# SCH_XILINX_JTAG-N_2022-10-28.net
KiCad netlist of a schematic drawn in EasyEDA
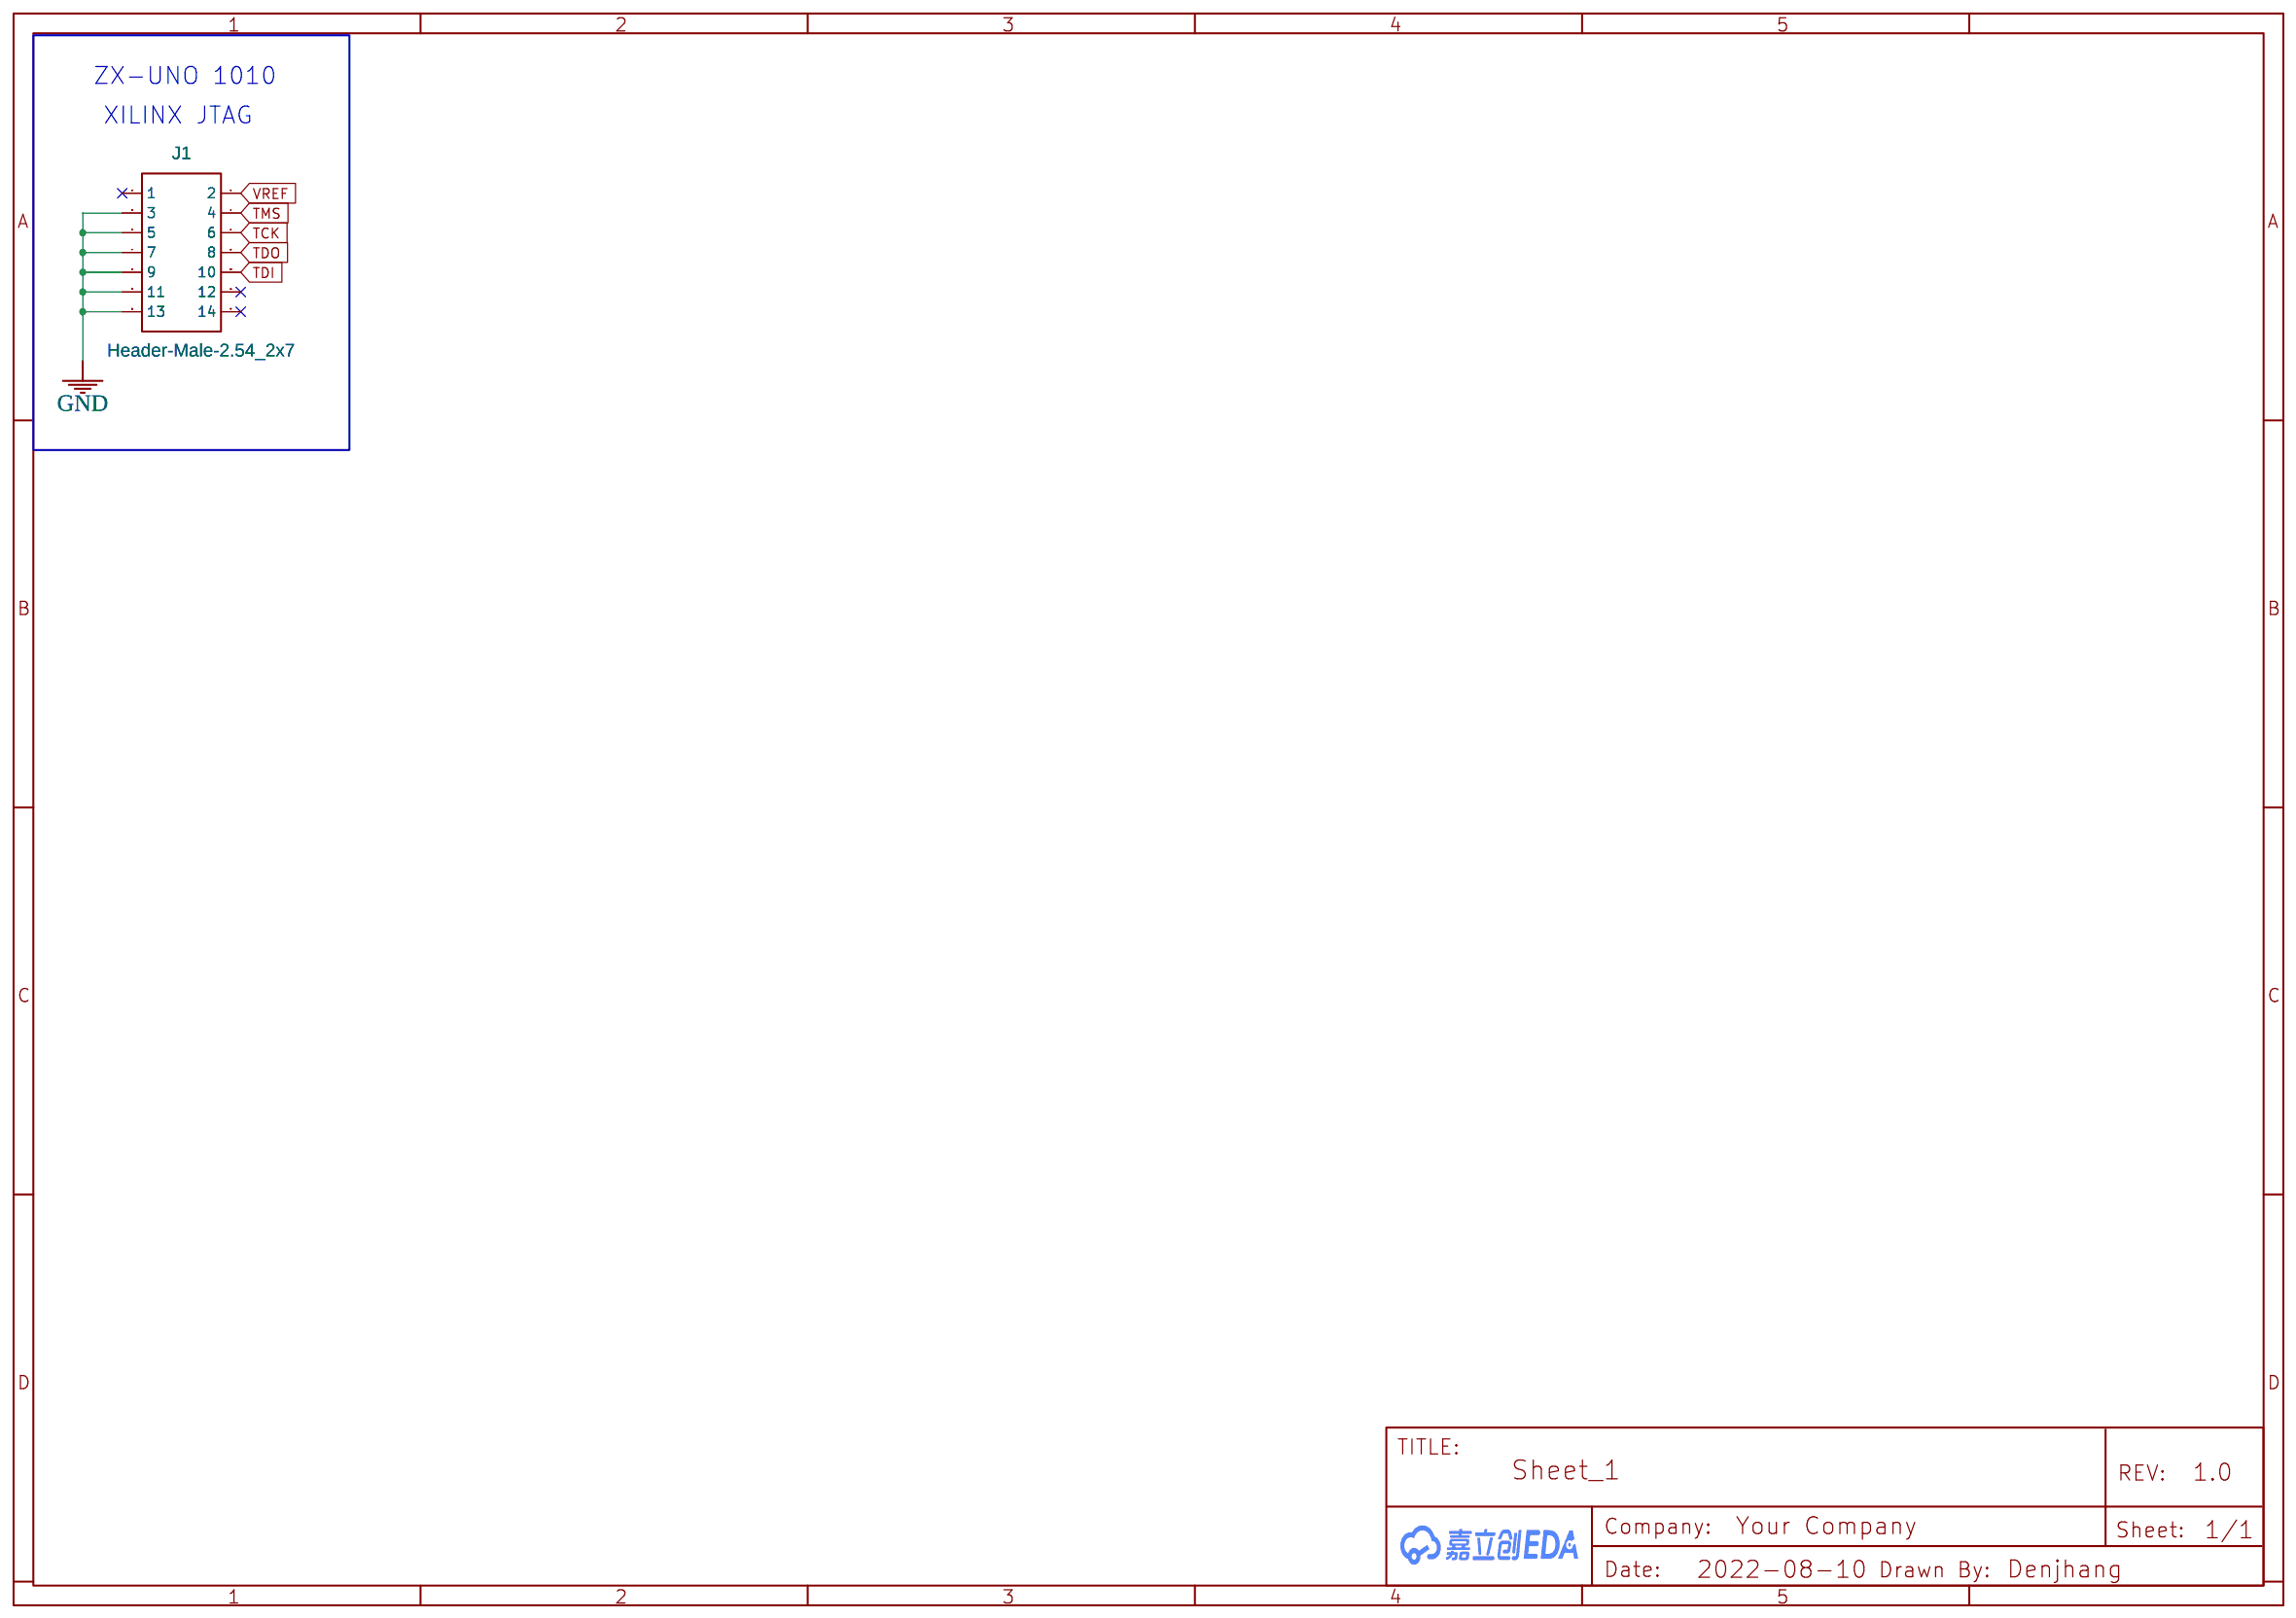
[diagram p0: MAIN]
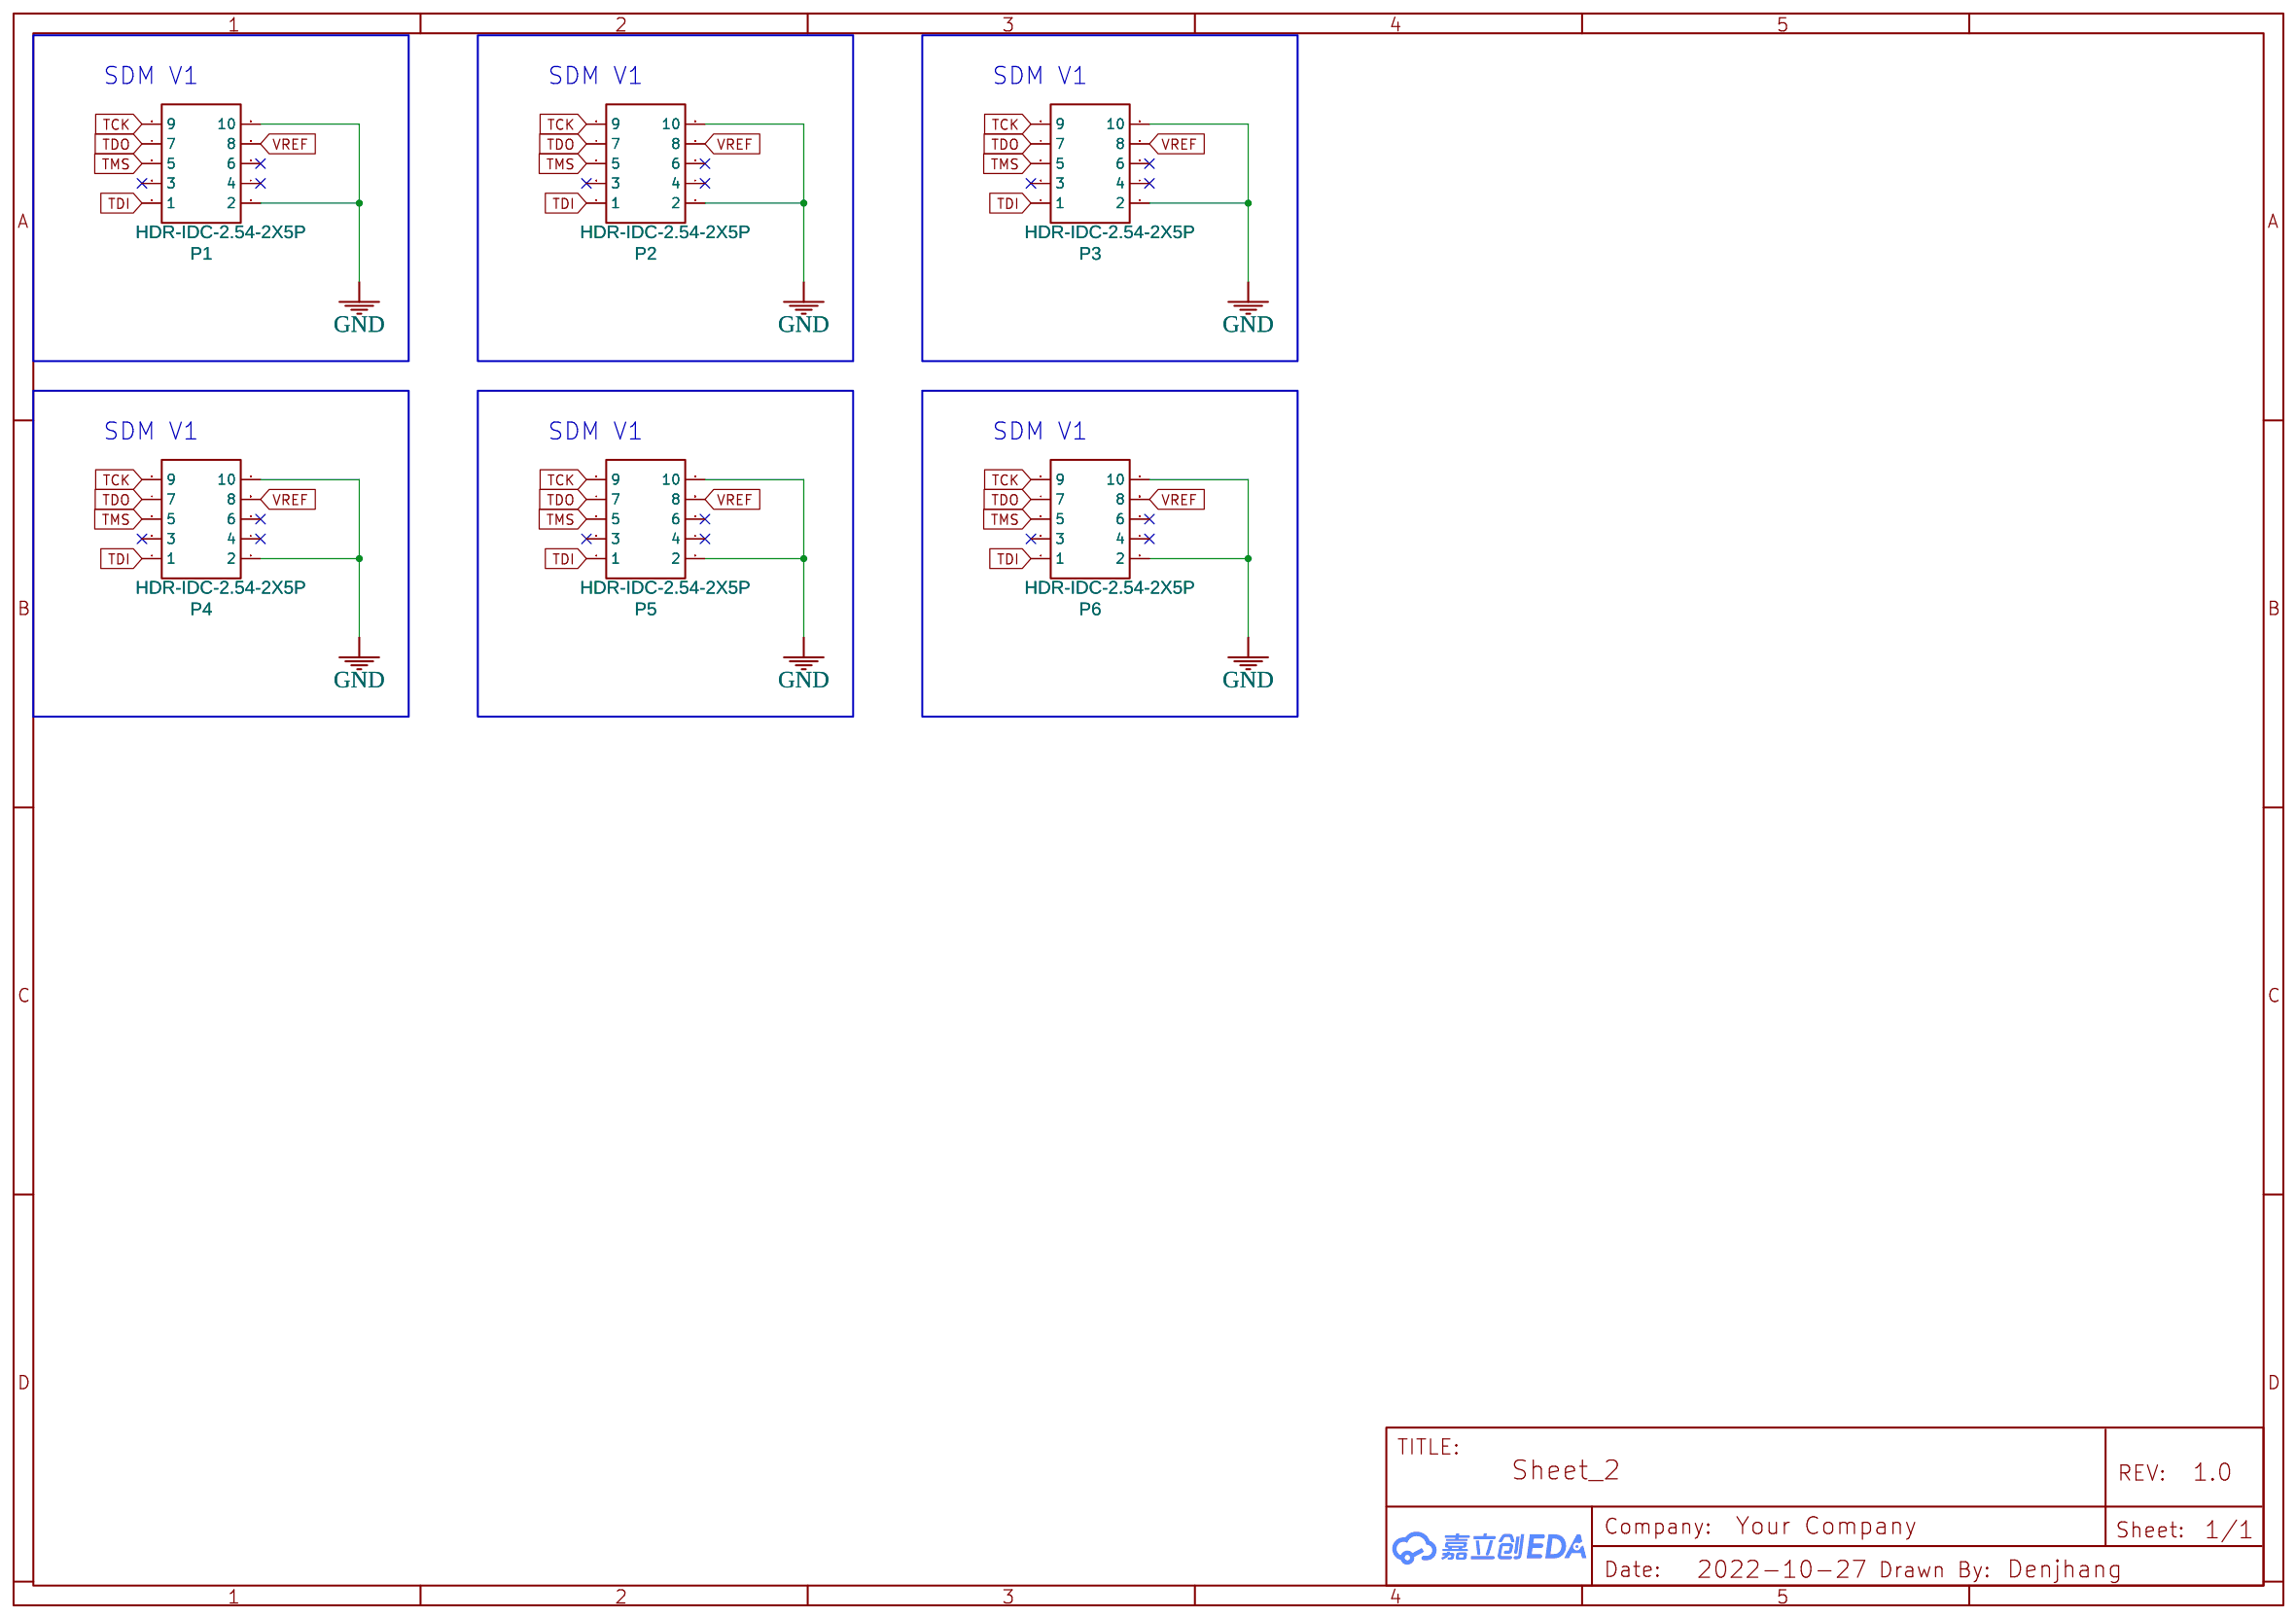
[diagram p1: SDMV1]
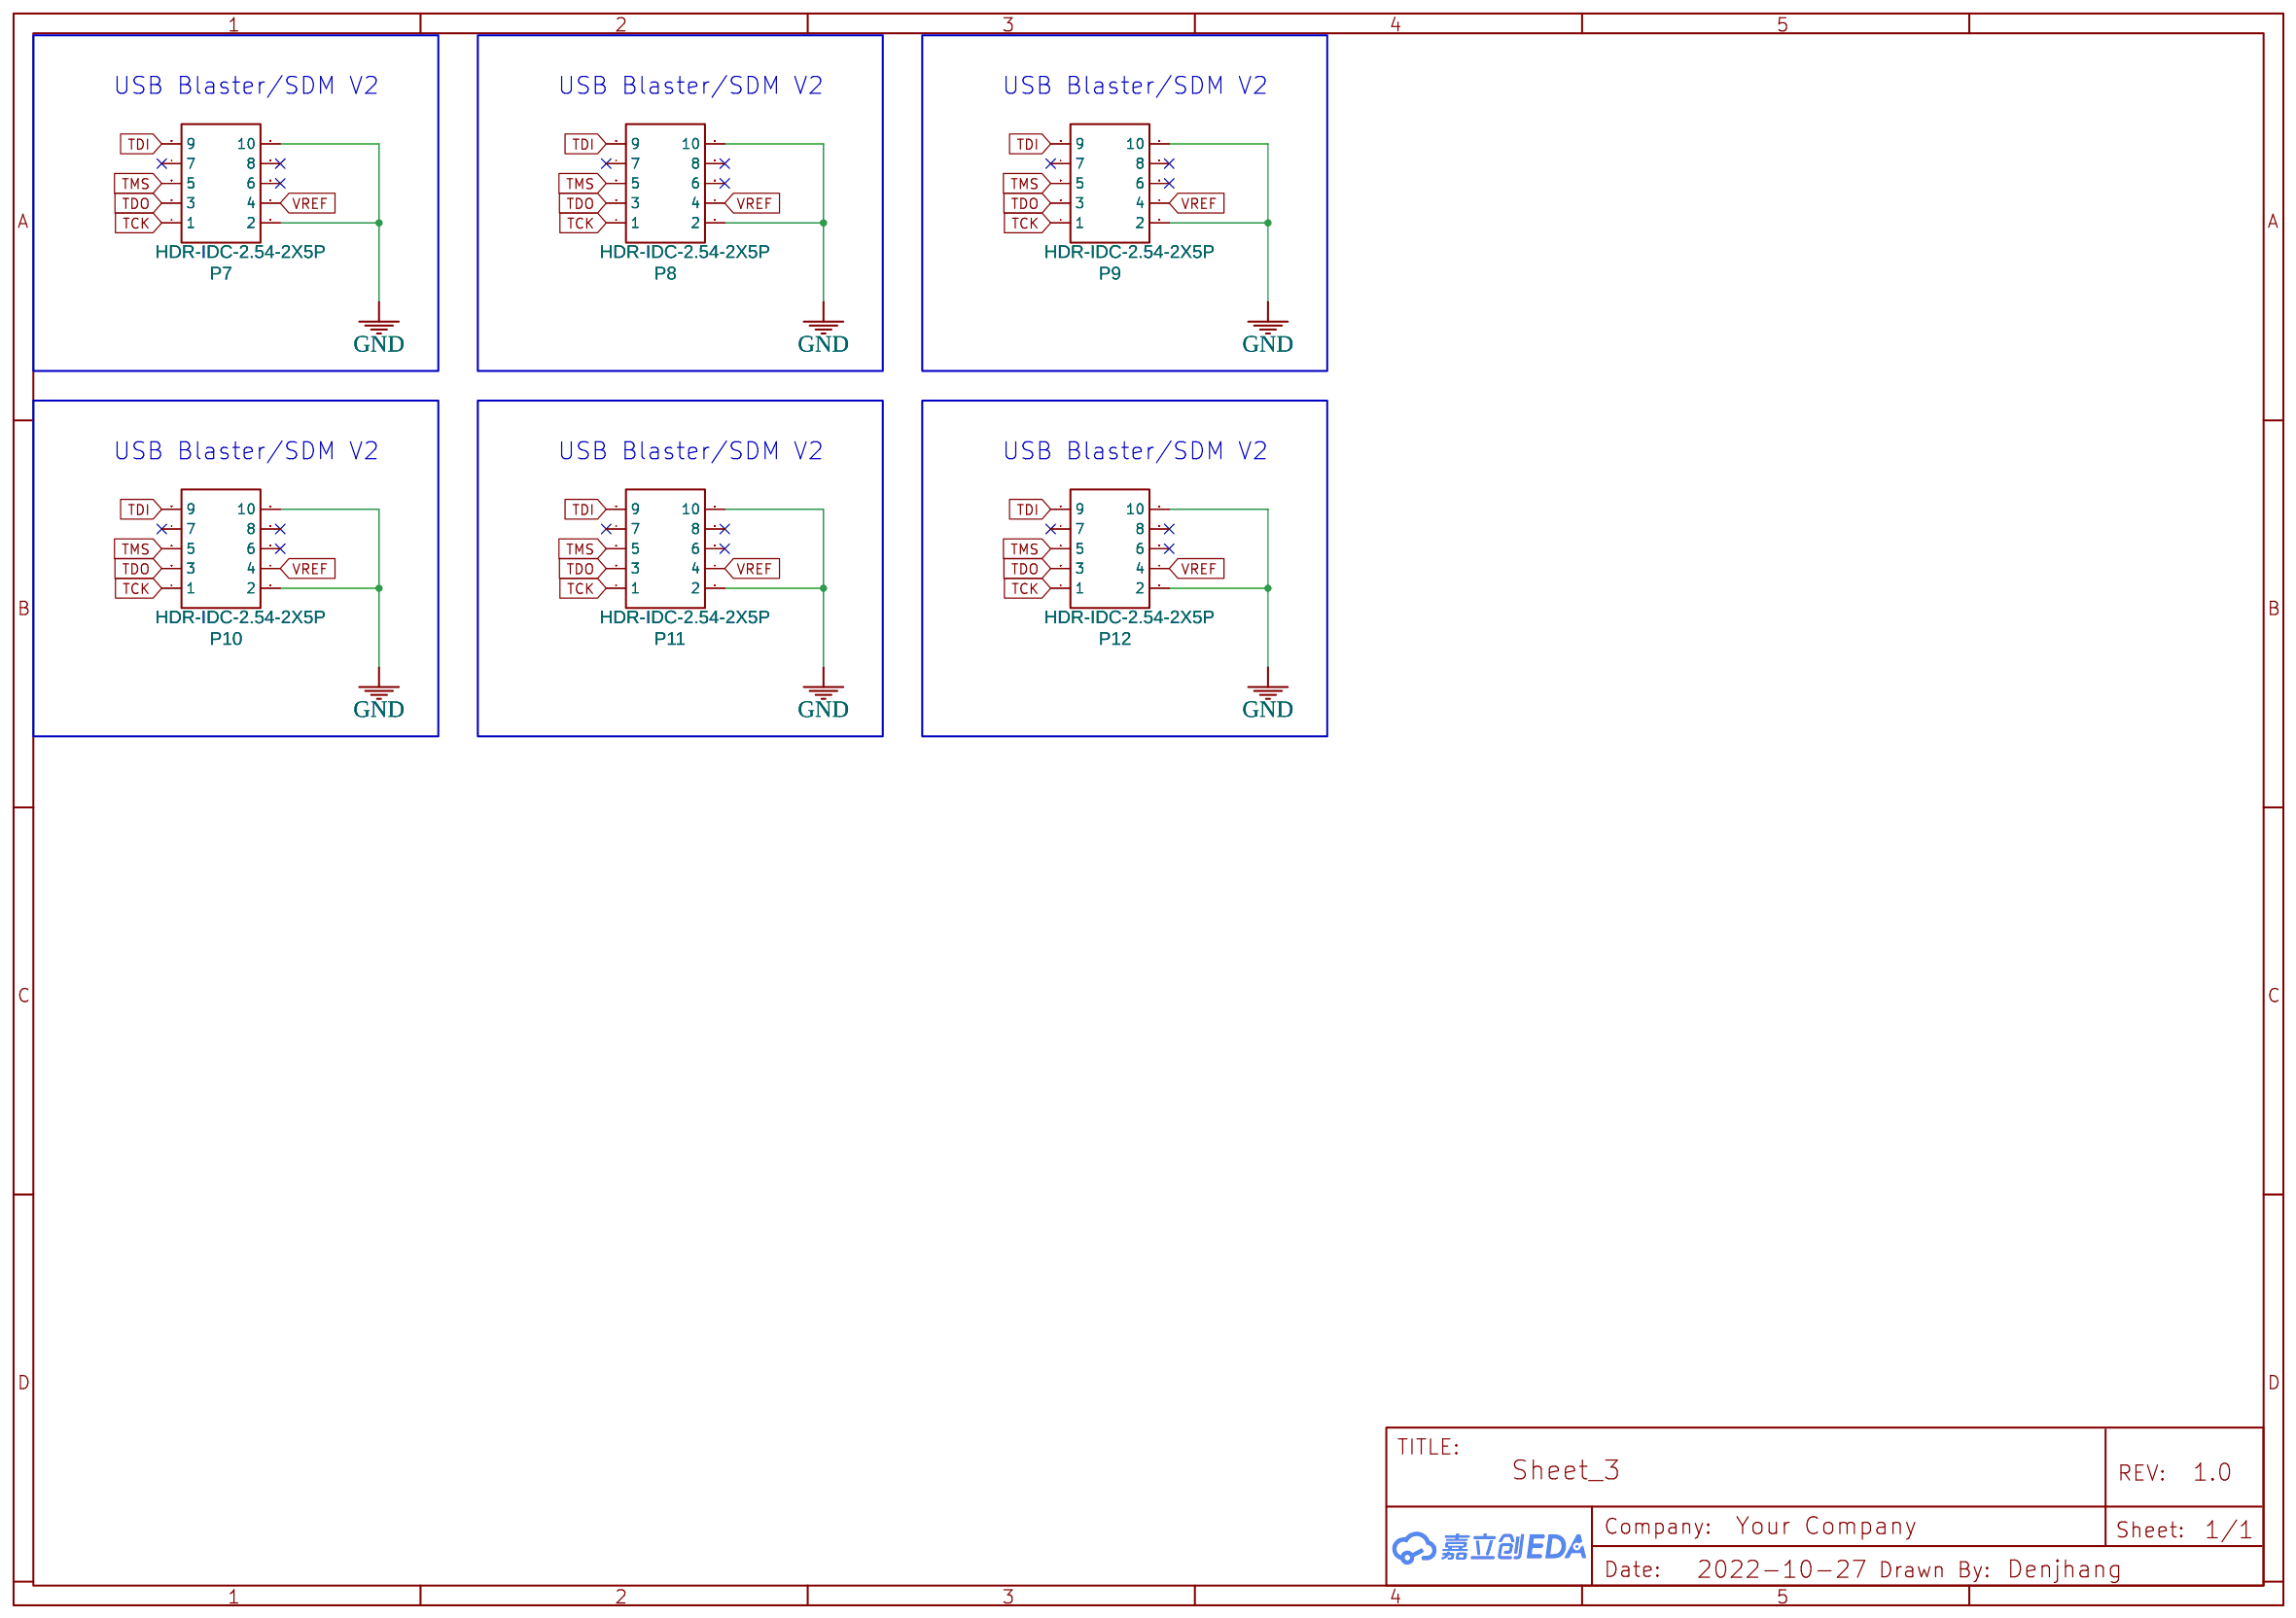
[diagram p2: SDMV2]

(export (version "E")
  (design (tool "Eeschema 10.0.6"))
  (components
    (comp (ref "J1")
      (value "Header-Male-2.54_2x7")
      (fields
        (field (name "BOM_Manufacturer Part") "Double row of needle2X7P 2.54mm")
        (field (name "BOM_Supplier Part") "C71397")
      )
      (libsource (lib "") (part "Header-Male-2.54_2x7"))
    )
    (comp (ref "P1")
      (value "HDR-IDC-2.54-2X5P")
      (fields
        (field (name "BOM_Manufacturer Part") "IDC Box 2.54mm 2X5P")
        (field (name "BOM_Supplier Part") "C5665")
      )
      (libsource (lib "") (part "HDR-IDC-2.54-2X5P"))
    )
    (comp (ref "P2")
      (value "HDR-IDC-2.54-2X5P")
      (fields
        (field (name "BOM_Manufacturer Part") "IDC Box 2.54mm 2X5P")
        (field (name "BOM_Supplier Part") "C5665")
      )
      (libsource (lib "") (part "HDR-IDC-2.54-2X5P"))
    )
    (comp (ref "P3")
      (value "HDR-IDC-2.54-2X5P")
      (fields
        (field (name "BOM_Manufacturer Part") "IDC Box 2.54mm 2X5P")
        (field (name "BOM_Supplier Part") "C5665")
      )
      (libsource (lib "") (part "HDR-IDC-2.54-2X5P"))
    )
    (comp (ref "P4")
      (value "HDR-IDC-2.54-2X5P")
      (fields
        (field (name "BOM_Manufacturer Part") "IDC Box 2.54mm 2X5P")
        (field (name "BOM_Supplier Part") "C5665")
      )
      (libsource (lib "") (part "HDR-IDC-2.54-2X5P"))
    )
    (comp (ref "P5")
      (value "HDR-IDC-2.54-2X5P")
      (fields
        (field (name "BOM_Manufacturer Part") "IDC Box 2.54mm 2X5P")
        (field (name "BOM_Supplier Part") "C5665")
      )
      (libsource (lib "") (part "HDR-IDC-2.54-2X5P"))
    )
    (comp (ref "P6")
      (value "HDR-IDC-2.54-2X5P")
      (fields
        (field (name "BOM_Manufacturer Part") "IDC Box 2.54mm 2X5P")
        (field (name "BOM_Supplier Part") "C5665")
      )
      (libsource (lib "") (part "HDR-IDC-2.54-2X5P"))
    )
    (comp (ref "P7")
      (value "HDR-IDC-2.54-2X5P")
      (fields
        (field (name "BOM_Manufacturer Part") "IDC Box 2.54mm 2X5P")
        (field (name "BOM_Supplier Part") "C5665")
      )
      (libsource (lib "") (part "HDR-IDC-2.54-2X5P"))
    )
    (comp (ref "P8")
      (value "HDR-IDC-2.54-2X5P")
      (fields
        (field (name "BOM_Manufacturer Part") "IDC Box 2.54mm 2X5P")
        (field (name "BOM_Supplier Part") "C5665")
      )
      (libsource (lib "") (part "HDR-IDC-2.54-2X5P"))
    )
    (comp (ref "P9")
      (value "HDR-IDC-2.54-2X5P")
      (fields
        (field (name "BOM_Manufacturer Part") "IDC Box 2.54mm 2X5P")
        (field (name "BOM_Supplier Part") "C5665")
      )
      (libsource (lib "") (part "HDR-IDC-2.54-2X5P"))
    )
    (comp (ref "P10")
      (value "HDR-IDC-2.54-2X5P")
      (fields
        (field (name "BOM_Manufacturer Part") "IDC Box 2.54mm 2X5P")
        (field (name "BOM_Supplier Part") "C5665")
      )
      (libsource (lib "") (part "HDR-IDC-2.54-2X5P"))
    )
    (comp (ref "P11")
      (value "HDR-IDC-2.54-2X5P")
      (fields
        (field (name "BOM_Manufacturer Part") "IDC Box 2.54mm 2X5P")
        (field (name "BOM_Supplier Part") "C5665")
      )
      (libsource (lib "") (part "HDR-IDC-2.54-2X5P"))
    )
    (comp (ref "P12")
      (value "HDR-IDC-2.54-2X5P")
      (fields
        (field (name "BOM_Manufacturer Part") "IDC Box 2.54mm 2X5P")
        (field (name "BOM_Supplier Part") "C5665")
      )
      (libsource (lib "") (part "HDR-IDC-2.54-2X5P"))
    )
  )
  (nets
    (net (code "1") (name "GND") (class "Default")
      (node (ref "J1") (pin "11") (pinfunction "11_11") (pintype "input"))
      (node (ref "J1") (pin "13") (pinfunction "13_13") (pintype "input"))
      (node (ref "J1") (pin "3") (pinfunction "3_3") (pintype "input"))
      (node (ref "J1") (pin "5") (pinfunction "5_5") (pintype "input"))
      (node (ref "J1") (pin "7") (pinfunction "7_7") (pintype "input"))
      (node (ref "J1") (pin "9") (pinfunction "9_9") (pintype "input"))
      (node (ref "P1") (pin "10") (pinfunction "10_10") (pintype "unspecified"))
      (node (ref "P1") (pin "2") (pinfunction "2_2") (pintype "unspecified"))
      (node (ref "P10") (pin "10") (pinfunction "10_10") (pintype "unspecified"))
      (node (ref "P10") (pin "2") (pinfunction "2_2") (pintype "unspecified"))
      (node (ref "P11") (pin "10") (pinfunction "10_10") (pintype "unspecified"))
      (node (ref "P11") (pin "2") (pinfunction "2_2") (pintype "unspecified"))
      (node (ref "P12") (pin "10") (pinfunction "10_10") (pintype "unspecified"))
      (node (ref "P12") (pin "2") (pinfunction "2_2") (pintype "unspecified"))
      (node (ref "P2") (pin "10") (pinfunction "10_10") (pintype "unspecified"))
      (node (ref "P2") (pin "2") (pinfunction "2_2") (pintype "unspecified"))
      (node (ref "P3") (pin "10") (pinfunction "10_10") (pintype "unspecified"))
      (node (ref "P3") (pin "2") (pinfunction "2_2") (pintype "unspecified"))
      (node (ref "P4") (pin "10") (pinfunction "10_10") (pintype "unspecified"))
      (node (ref "P4") (pin "2") (pinfunction "2_2") (pintype "unspecified"))
      (node (ref "P5") (pin "10") (pinfunction "10_10") (pintype "unspecified"))
      (node (ref "P5") (pin "2") (pinfunction "2_2") (pintype "unspecified"))
      (node (ref "P6") (pin "10") (pinfunction "10_10") (pintype "unspecified"))
      (node (ref "P6") (pin "2") (pinfunction "2_2") (pintype "unspecified"))
      (node (ref "P7") (pin "10") (pinfunction "10_10") (pintype "unspecified"))
      (node (ref "P7") (pin "2") (pinfunction "2_2") (pintype "unspecified"))
      (node (ref "P8") (pin "10") (pinfunction "10_10") (pintype "unspecified"))
      (node (ref "P8") (pin "2") (pinfunction "2_2") (pintype "unspecified"))
      (node (ref "P9") (pin "10") (pinfunction "10_10") (pintype "unspecified"))
      (node (ref "P9") (pin "2") (pinfunction "2_2") (pintype "unspecified"))
    )
    (net (code "2") (name "TCK") (class "Default")
      (node (ref "J1") (pin "6") (pinfunction "6_6") (pintype "input"))
      (node (ref "P1") (pin "9") (pinfunction "9_9") (pintype "unspecified"))
      (node (ref "P10") (pin "1") (pinfunction "1_1") (pintype "unspecified"))
      (node (ref "P11") (pin "1") (pinfunction "1_1") (pintype "unspecified"))
      (node (ref "P12") (pin "1") (pinfunction "1_1") (pintype "unspecified"))
      (node (ref "P2") (pin "9") (pinfunction "9_9") (pintype "unspecified"))
      (node (ref "P3") (pin "9") (pinfunction "9_9") (pintype "unspecified"))
      (node (ref "P4") (pin "9") (pinfunction "9_9") (pintype "unspecified"))
      (node (ref "P5") (pin "9") (pinfunction "9_9") (pintype "unspecified"))
      (node (ref "P6") (pin "9") (pinfunction "9_9") (pintype "unspecified"))
      (node (ref "P7") (pin "1") (pinfunction "1_1") (pintype "unspecified"))
      (node (ref "P8") (pin "1") (pinfunction "1_1") (pintype "unspecified"))
      (node (ref "P9") (pin "1") (pinfunction "1_1") (pintype "unspecified"))
    )
    (net (code "3") (name "TDI") (class "Default")
      (node (ref "J1") (pin "10") (pinfunction "10_10") (pintype "input"))
      (node (ref "P1") (pin "1") (pinfunction "1_1") (pintype "unspecified"))
      (node (ref "P10") (pin "9") (pinfunction "9_9") (pintype "unspecified"))
      (node (ref "P11") (pin "9") (pinfunction "9_9") (pintype "unspecified"))
      (node (ref "P12") (pin "9") (pinfunction "9_9") (pintype "unspecified"))
      (node (ref "P2") (pin "1") (pinfunction "1_1") (pintype "unspecified"))
      (node (ref "P3") (pin "1") (pinfunction "1_1") (pintype "unspecified"))
      (node (ref "P4") (pin "1") (pinfunction "1_1") (pintype "unspecified"))
      (node (ref "P5") (pin "1") (pinfunction "1_1") (pintype "unspecified"))
      (node (ref "P6") (pin "1") (pinfunction "1_1") (pintype "unspecified"))
      (node (ref "P7") (pin "9") (pinfunction "9_9") (pintype "unspecified"))
      (node (ref "P8") (pin "9") (pinfunction "9_9") (pintype "unspecified"))
      (node (ref "P9") (pin "9") (pinfunction "9_9") (pintype "unspecified"))
    )
    (net (code "4") (name "TDO") (class "Default")
      (node (ref "J1") (pin "8") (pinfunction "8_8") (pintype "input"))
      (node (ref "P1") (pin "7") (pinfunction "7_7") (pintype "unspecified"))
      (node (ref "P10") (pin "3") (pinfunction "3_3") (pintype "unspecified"))
      (node (ref "P11") (pin "3") (pinfunction "3_3") (pintype "unspecified"))
      (node (ref "P12") (pin "3") (pinfunction "3_3") (pintype "unspecified"))
      (node (ref "P2") (pin "7") (pinfunction "7_7") (pintype "unspecified"))
      (node (ref "P3") (pin "7") (pinfunction "7_7") (pintype "unspecified"))
      (node (ref "P4") (pin "7") (pinfunction "7_7") (pintype "unspecified"))
      (node (ref "P5") (pin "7") (pinfunction "7_7") (pintype "unspecified"))
      (node (ref "P6") (pin "7") (pinfunction "7_7") (pintype "unspecified"))
      (node (ref "P7") (pin "3") (pinfunction "3_3") (pintype "unspecified"))
      (node (ref "P8") (pin "3") (pinfunction "3_3") (pintype "unspecified"))
      (node (ref "P9") (pin "3") (pinfunction "3_3") (pintype "unspecified"))
    )
    (net (code "5") (name "TMS") (class "Default")
      (node (ref "J1") (pin "4") (pinfunction "4_4") (pintype "input"))
      (node (ref "P1") (pin "5") (pinfunction "5_5") (pintype "unspecified"))
      (node (ref "P10") (pin "5") (pinfunction "5_5") (pintype "unspecified"))
      (node (ref "P11") (pin "5") (pinfunction "5_5") (pintype "unspecified"))
      (node (ref "P12") (pin "5") (pinfunction "5_5") (pintype "unspecified"))
      (node (ref "P2") (pin "5") (pinfunction "5_5") (pintype "unspecified"))
      (node (ref "P3") (pin "5") (pinfunction "5_5") (pintype "unspecified"))
      (node (ref "P4") (pin "5") (pinfunction "5_5") (pintype "unspecified"))
      (node (ref "P5") (pin "5") (pinfunction "5_5") (pintype "unspecified"))
      (node (ref "P6") (pin "5") (pinfunction "5_5") (pintype "unspecified"))
      (node (ref "P7") (pin "5") (pinfunction "5_5") (pintype "unspecified"))
      (node (ref "P8") (pin "5") (pinfunction "5_5") (pintype "unspecified"))
      (node (ref "P9") (pin "5") (pinfunction "5_5") (pintype "unspecified"))
    )
    (net (code "6") (name "VREF") (class "Default")
      (node (ref "J1") (pin "2") (pinfunction "2_2") (pintype "input"))
      (node (ref "P1") (pin "8") (pinfunction "8_8") (pintype "unspecified"))
      (node (ref "P10") (pin "4") (pinfunction "4_4") (pintype "unspecified"))
      (node (ref "P11") (pin "4") (pinfunction "4_4") (pintype "unspecified"))
      (node (ref "P12") (pin "4") (pinfunction "4_4") (pintype "unspecified"))
      (node (ref "P2") (pin "8") (pinfunction "8_8") (pintype "unspecified"))
      (node (ref "P3") (pin "8") (pinfunction "8_8") (pintype "unspecified"))
      (node (ref "P4") (pin "8") (pinfunction "8_8") (pintype "unspecified"))
      (node (ref "P5") (pin "8") (pinfunction "8_8") (pintype "unspecified"))
      (node (ref "P6") (pin "8") (pinfunction "8_8") (pintype "unspecified"))
      (node (ref "P7") (pin "4") (pinfunction "4_4") (pintype "unspecified"))
      (node (ref "P8") (pin "4") (pinfunction "4_4") (pintype "unspecified"))
      (node (ref "P9") (pin "4") (pinfunction "4_4") (pintype "unspecified"))
    )
    (net (code "7") (name "unconnected-(J1-Pad1)") (class "Default")
      (node (ref "J1") (pin "1") (pinfunction "1_1") (pintype "input+no_connect"))
    )
    (net (code "8") (name "unconnected-(J1-Pad12)") (class "Default")
      (node (ref "J1") (pin "12") (pinfunction "12_12") (pintype "input+no_connect"))
    )
    (net (code "9") (name "unconnected-(J1-Pad14)") (class "Default")
      (node (ref "J1") (pin "14") (pinfunction "14_14") (pintype "input+no_connect"))
    )
    (net (code "10") (name "unconnected-(P1-Pad3)") (class "Default")
      (node (ref "P1") (pin "3") (pinfunction "3_3") (pintype "unspecified+no_connect"))
    )
    (net (code "11") (name "unconnected-(P1-Pad4)") (class "Default")
      (node (ref "P1") (pin "4") (pinfunction "4_4") (pintype "unspecified+no_connect"))
    )
    (net (code "12") (name "unconnected-(P1-Pad6)") (class "Default")
      (node (ref "P1") (pin "6") (pinfunction "6_6") (pintype "unspecified+no_connect"))
    )
    (net (code "13") (name "unconnected-(P2-Pad3)") (class "Default")
      (node (ref "P2") (pin "3") (pinfunction "3_3") (pintype "unspecified+no_connect"))
    )
    (net (code "14") (name "unconnected-(P2-Pad4)") (class "Default")
      (node (ref "P2") (pin "4") (pinfunction "4_4") (pintype "unspecified+no_connect"))
    )
    (net (code "15") (name "unconnected-(P2-Pad6)") (class "Default")
      (node (ref "P2") (pin "6") (pinfunction "6_6") (pintype "unspecified+no_connect"))
    )
    (net (code "16") (name "unconnected-(P3-Pad3)") (class "Default")
      (node (ref "P3") (pin "3") (pinfunction "3_3") (pintype "unspecified+no_connect"))
    )
    (net (code "17") (name "unconnected-(P3-Pad4)") (class "Default")
      (node (ref "P3") (pin "4") (pinfunction "4_4") (pintype "unspecified+no_connect"))
    )
    (net (code "18") (name "unconnected-(P3-Pad6)") (class "Default")
      (node (ref "P3") (pin "6") (pinfunction "6_6") (pintype "unspecified+no_connect"))
    )
    (net (code "19") (name "unconnected-(P4-Pad3)") (class "Default")
      (node (ref "P4") (pin "3") (pinfunction "3_3") (pintype "unspecified+no_connect"))
    )
    (net (code "20") (name "unconnected-(P4-Pad4)") (class "Default")
      (node (ref "P4") (pin "4") (pinfunction "4_4") (pintype "unspecified+no_connect"))
    )
    (net (code "21") (name "unconnected-(P4-Pad6)") (class "Default")
      (node (ref "P4") (pin "6") (pinfunction "6_6") (pintype "unspecified+no_connect"))
    )
    (net (code "22") (name "unconnected-(P5-Pad3)") (class "Default")
      (node (ref "P5") (pin "3") (pinfunction "3_3") (pintype "unspecified+no_connect"))
    )
    (net (code "23") (name "unconnected-(P5-Pad4)") (class "Default")
      (node (ref "P5") (pin "4") (pinfunction "4_4") (pintype "unspecified+no_connect"))
    )
    (net (code "24") (name "unconnected-(P5-Pad6)") (class "Default")
      (node (ref "P5") (pin "6") (pinfunction "6_6") (pintype "unspecified+no_connect"))
    )
    (net (code "25") (name "unconnected-(P6-Pad3)") (class "Default")
      (node (ref "P6") (pin "3") (pinfunction "3_3") (pintype "unspecified+no_connect"))
    )
    (net (code "26") (name "unconnected-(P6-Pad4)") (class "Default")
      (node (ref "P6") (pin "4") (pinfunction "4_4") (pintype "unspecified+no_connect"))
    )
    (net (code "27") (name "unconnected-(P6-Pad6)") (class "Default")
      (node (ref "P6") (pin "6") (pinfunction "6_6") (pintype "unspecified+no_connect"))
    )
    (net (code "28") (name "unconnected-(P7-Pad6)") (class "Default")
      (node (ref "P7") (pin "6") (pinfunction "6_6") (pintype "unspecified+no_connect"))
    )
    (net (code "29") (name "unconnected-(P7-Pad7)") (class "Default")
      (node (ref "P7") (pin "7") (pinfunction "7_7") (pintype "unspecified+no_connect"))
    )
    (net (code "30") (name "unconnected-(P7-Pad8)") (class "Default")
      (node (ref "P7") (pin "8") (pinfunction "8_8") (pintype "unspecified+no_connect"))
    )
    (net (code "31") (name "unconnected-(P8-Pad6)") (class "Default")
      (node (ref "P8") (pin "6") (pinfunction "6_6") (pintype "unspecified+no_connect"))
    )
    (net (code "32") (name "unconnected-(P8-Pad7)") (class "Default")
      (node (ref "P8") (pin "7") (pinfunction "7_7") (pintype "unspecified+no_connect"))
    )
    (net (code "33") (name "unconnected-(P8-Pad8)") (class "Default")
      (node (ref "P8") (pin "8") (pinfunction "8_8") (pintype "unspecified+no_connect"))
    )
    (net (code "34") (name "unconnected-(P9-Pad6)") (class "Default")
      (node (ref "P9") (pin "6") (pinfunction "6_6") (pintype "unspecified+no_connect"))
    )
    (net (code "35") (name "unconnected-(P9-Pad7)") (class "Default")
      (node (ref "P9") (pin "7") (pinfunction "7_7") (pintype "unspecified+no_connect"))
    )
    (net (code "36") (name "unconnected-(P9-Pad8)") (class "Default")
      (node (ref "P9") (pin "8") (pinfunction "8_8") (pintype "unspecified+no_connect"))
    )
    (net (code "37") (name "unconnected-(P10-Pad6)") (class "Default")
      (node (ref "P10") (pin "6") (pinfunction "6_6") (pintype "unspecified+no_connect"))
    )
    (net (code "38") (name "unconnected-(P10-Pad7)") (class "Default")
      (node (ref "P10") (pin "7") (pinfunction "7_7") (pintype "unspecified+no_connect"))
    )
    (net (code "39") (name "unconnected-(P10-Pad8)") (class "Default")
      (node (ref "P10") (pin "8") (pinfunction "8_8") (pintype "unspecified+no_connect"))
    )
    (net (code "40") (name "unconnected-(P11-Pad6)") (class "Default")
      (node (ref "P11") (pin "6") (pinfunction "6_6") (pintype "unspecified+no_connect"))
    )
    (net (code "41") (name "unconnected-(P11-Pad7)") (class "Default")
      (node (ref "P11") (pin "7") (pinfunction "7_7") (pintype "unspecified+no_connect"))
    )
    (net (code "42") (name "unconnected-(P11-Pad8)") (class "Default")
      (node (ref "P11") (pin "8") (pinfunction "8_8") (pintype "unspecified+no_connect"))
    )
    (net (code "43") (name "unconnected-(P12-Pad6)") (class "Default")
      (node (ref "P12") (pin "6") (pinfunction "6_6") (pintype "unspecified+no_connect"))
    )
    (net (code "44") (name "unconnected-(P12-Pad7)") (class "Default")
      (node (ref "P12") (pin "7") (pinfunction "7_7") (pintype "unspecified+no_connect"))
    )
    (net (code "45") (name "unconnected-(P12-Pad8)") (class "Default")
      (node (ref "P12") (pin "8") (pinfunction "8_8") (pintype "unspecified+no_connect"))
    )
  )
)
